# Other.net
KiCad netlist of a schematic drawn in Altium Designer
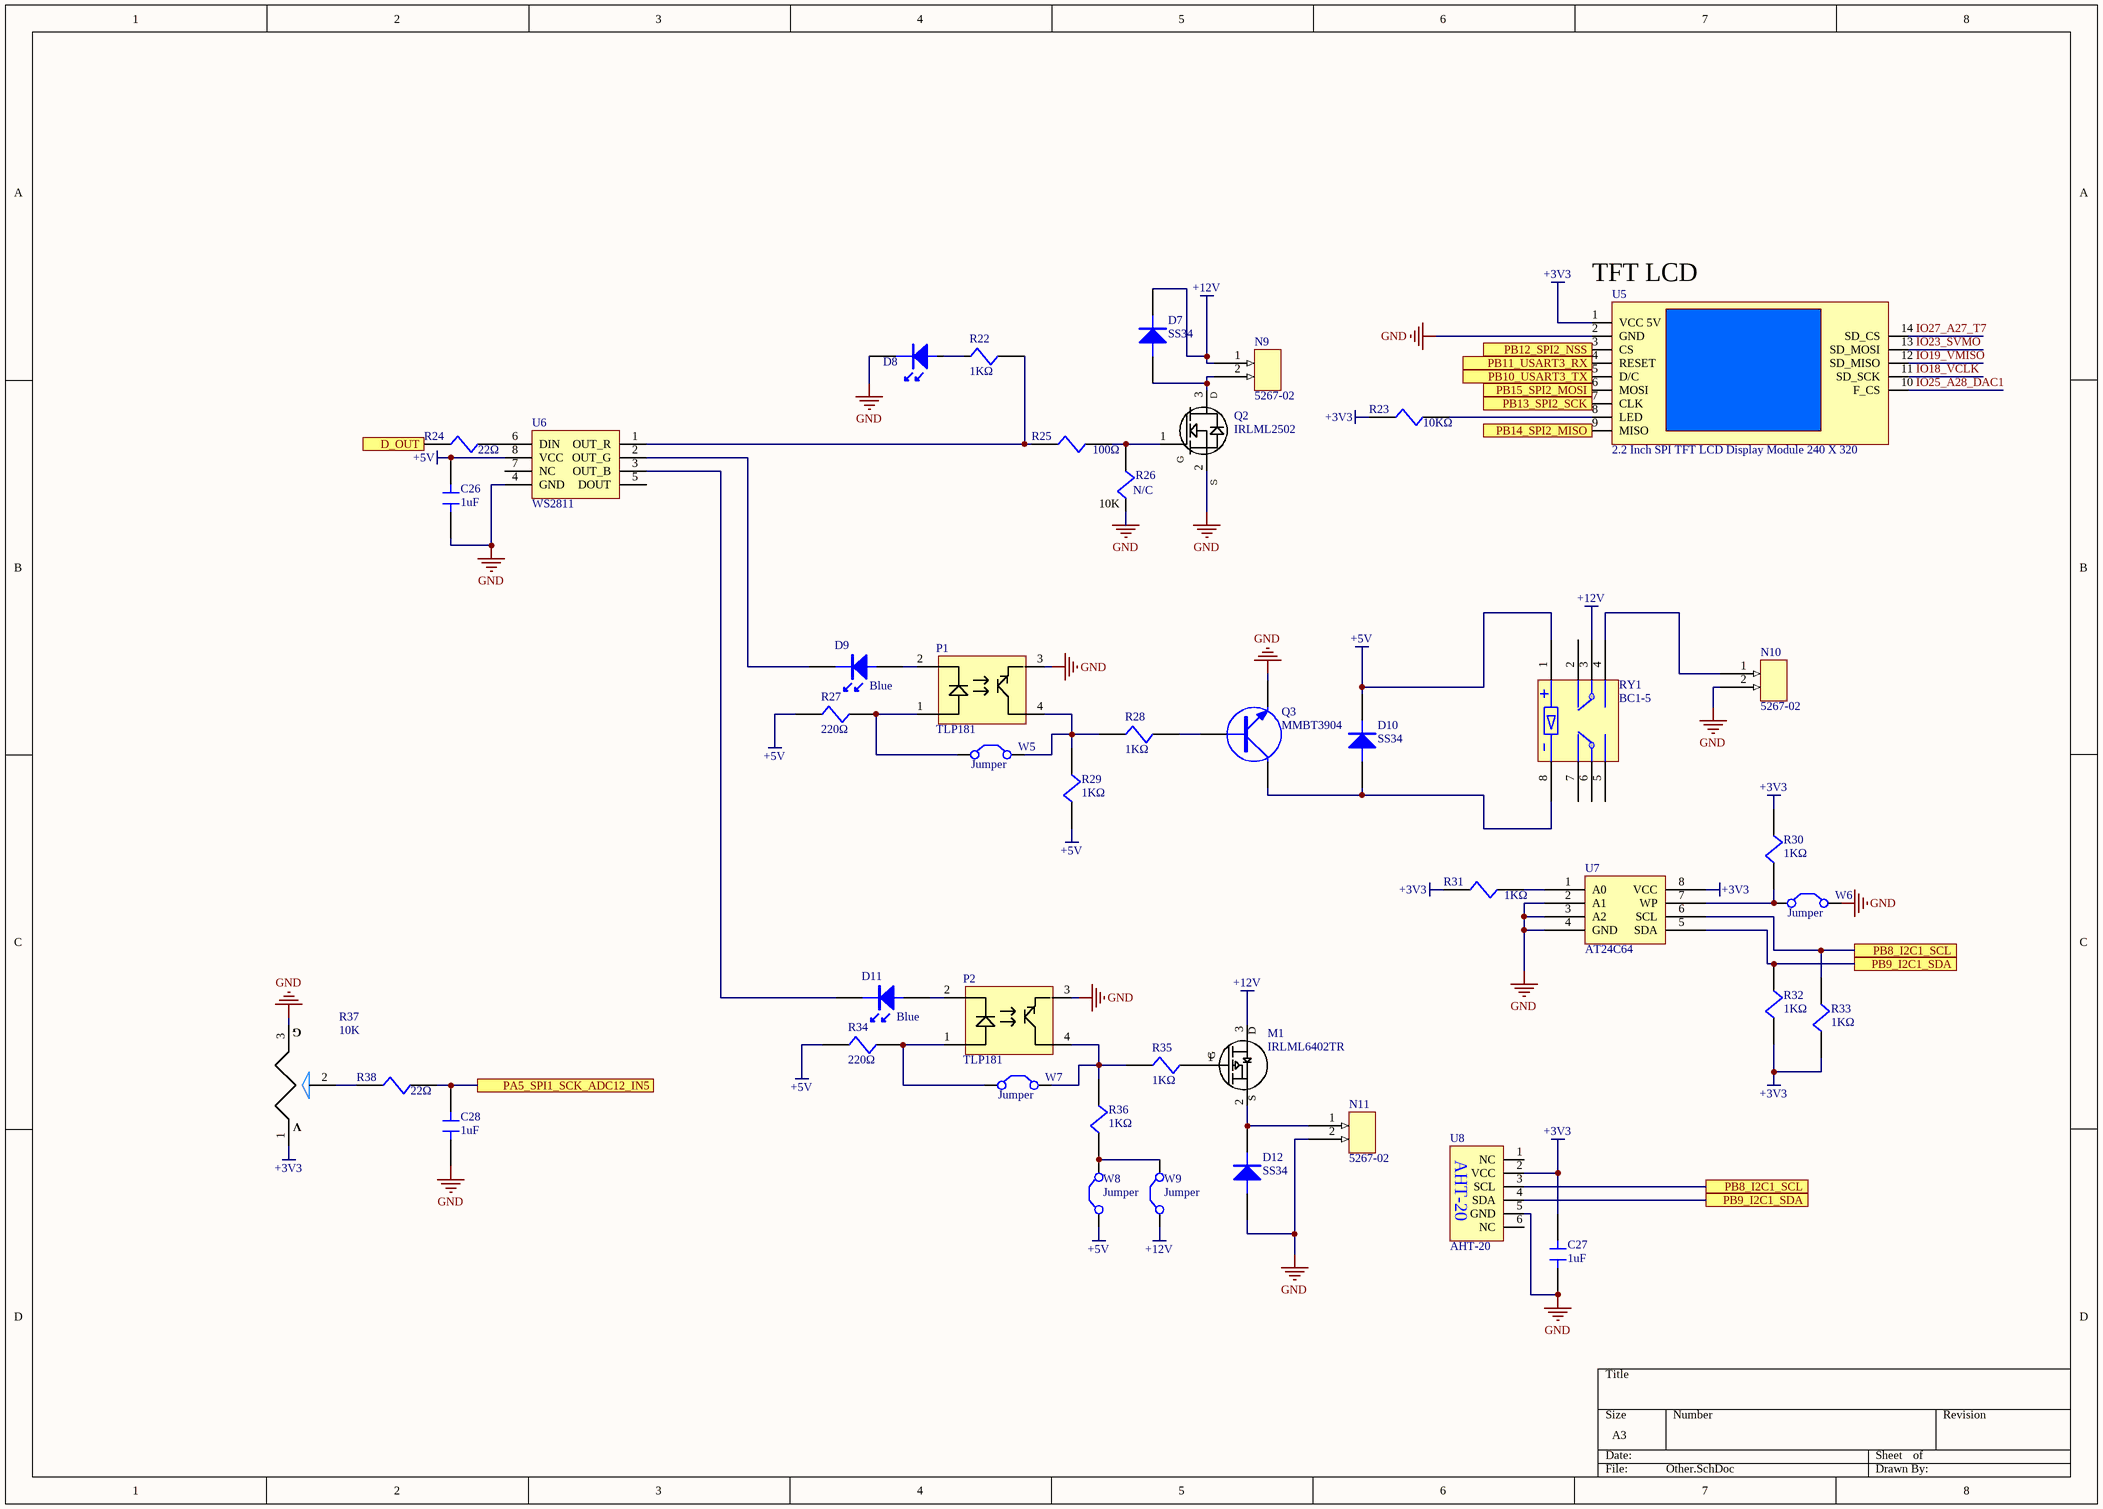
[diagram p0: Other.SchDoc]

(export (version "E")
  (design (tool "Eeschema 10.0.6"))
  (components
    (comp (ref "C26")
      (value "Chip Capacitor")
      (footprint "1608-C")
      (description "Capacitor, 1608 type")
      (fields (field (name "PART NUMBER") "1uF"))
      (libsource (lib "*") (part "CAP"))
    )
    (comp (ref "C27")
      (value "Chip Capacitor")
      (footprint "1608-C")
      (description "Capacitor, 1608 type")
      (fields (field (name "PART NUMBER") "1uF"))
      (libsource (lib "*") (part "CAP"))
    )
    (comp (ref "C28")
      (value "Chip Capacitor")
      (footprint "1608-C")
      (description "Capacitor, 1608 type")
      (fields (field (name "PART NUMBER") "1uF"))
      (libsource (lib "*") (part "CAP"))
    )
    (comp (ref "D7")
      (value "DIODE")
      (footprint "SS34")
      (fields (field (name "PART NUMBER") "SS34"))
      (libsource (lib "SCH_LIB") (part "DIODE"))
    )
    (comp (ref "D8")
      (value "LED")
      (footprint "1608-LED")
      (description "Green, 1608. SMD")
      (libsource (lib "SCH_LIB") (part "LED"))
    )
    (comp (ref "D9")
      (value "Chip LED")
      (footprint "1608-LED")
      (description "1608 Chip LED")
      (fields (field (name "PART NUMBER") "Blue"))
      (libsource (lib "SCH_LIB") (part "LED"))
    )
    (comp (ref "D10")
      (value "DIODE")
      (footprint "SS34")
      (fields (field (name "PART NUMBER") "SS34"))
      (libsource (lib "SCH_LIB") (part "DIODE"))
    )
    (comp (ref "D11")
      (value "Chip LED")
      (footprint "1608-LED")
      (description "1608 Chip LED")
      (fields (field (name "PART NUMBER") "Blue"))
      (libsource (lib "SCH_LIB") (part "LED"))
    )
    (comp (ref "D12")
      (value "DIODE")
      (footprint "SS34")
      (fields (field (name "PART NUMBER") "SS34"))
      (libsource (lib "SCH_LIB") (part "DIODE"))
    )
    (comp (ref "M1")
      (value "MOSPET-P")
      (footprint "Micro3")
      (description "P-Channel MOSFET")
      (fields (field (name "PART NUMBER") "IRLML6402TR"))
      (libsource (lib "SEMIN_LIB_SCH") (part "MOSPET-P"))
    )
    (comp (ref "N9")
      (value "CONNECTOR")
      (footprint "5267-02")
      (description "Molex")
      (fields (field (name "PART NUMBER") "5267-02"))
      (libsource (lib "SCH_LIB") (part "CON2"))
    )
    (comp (ref "N10")
      (value "CONNECTOR")
      (footprint "5267-02")
      (description "Molex")
      (fields (field (name "PART NUMBER") "5267-02"))
      (libsource (lib "SCH_LIB") (part "CON2"))
    )
    (comp (ref "N11")
      (value "CONNECTOR")
      (footprint "5267-02")
      (description "Molex")
      (fields (field (name "PART NUMBER") "5267-02"))
      (libsource (lib "SCH_LIB") (part "CON2"))
    )
    (comp (ref "P1")
      (value "Photo_Coupler")
      (footprint "TLP181")
      (description "1CH_small coupler")
      (fields (field (name "PART NUMBER") "TLP181"))
      (libsource (lib "SEMIN_LIB_SCH") (part "Photo_Coupler"))
    )
    (comp (ref "P2")
      (value "Photo_Coupler")
      (footprint "TLP181")
      (description "1CH_small coupler")
      (fields (field (name "PART NUMBER") "TLP181"))
      (libsource (lib "SEMIN_LIB_SCH") (part "Photo_Coupler"))
    )
    (comp (ref "Q2")
      (value "N_FET")
      (footprint "SOT_23_BIG")
      (description "N Chnel FET")
      (fields (field (name "PART NUMBER") "IRLML2502"))
      (libsource (lib "SEMIN_LIB_SCH") (part "IRLML2502"))
    )
    (comp (ref "Q3")
      (value "NPN TR")
      (footprint "SOT-23TR")
      (description "Transistor")
      (fields (field (name "PART NUMBER") "MMBT3904"))
      (libsource (lib "SCH_LIB") (part "TR(NPN)"))
    )
    (comp (ref "R22")
      (value "Chip Resistor")
      (footprint "1608-R")
      (description "Resistor, 1608 type")
      (fields (field (name "PART NUMBER") "1KΩ"))
      (libsource (lib "*") (part "RES1"))
    )
    (comp (ref "R23")
      (value "Chip Resistor")
      (footprint "1608-R")
      (description "Resistor, 1608 type")
      (fields (field (name "PART NUMBER") "10KΩ"))
      (libsource (lib "*") (part "RES1"))
    )
    (comp (ref "R24")
      (value "Chip Resistor")
      (footprint "1608-R")
      (description "Resistor, 1608 type")
      (fields (field (name "PART NUMBER") "22Ω"))
      (libsource (lib "*") (part "RES1"))
    )
    (comp (ref "R25")
      (value "Chip Resistor")
      (footprint "1608-R")
      (description "Resistor, 1608 type")
      (fields (field (name "PART NUMBER") "100Ω"))
      (libsource (lib "*") (part "RES1"))
    )
    (comp (ref "R26")
      (value "Chip Resistor")
      (footprint "1608-R")
      (description "Resistor, 1608 type")
      (fields (field (name "PART NUMBER") "N/C"))
      (libsource (lib "*") (part "RES1"))
    )
    (comp (ref "R27")
      (value "Chip Resistor")
      (footprint "1608-R")
      (description "Resistor, 1608 type")
      (fields (field (name "PART NUMBER") "220Ω"))
      (libsource (lib "*") (part "RES1"))
    )
    (comp (ref "R28")
      (value "Chip Resistor")
      (footprint "1608-R")
      (description "Resistor, 1608 type")
      (fields (field (name "PART NUMBER") "1KΩ"))
      (libsource (lib "*") (part "RES1"))
    )
    (comp (ref "R29")
      (value "Chip Resistor")
      (footprint "1608-R")
      (description "Resistor, 1608 type")
      (fields (field (name "PART NUMBER") "1KΩ"))
      (libsource (lib "*") (part "RES1"))
    )
    (comp (ref "R30")
      (value "Chip Resistor")
      (footprint "1608-R")
      (description "Resistor, 1608 type")
      (fields (field (name "PART NUMBER") "1KΩ"))
      (libsource (lib "*") (part "RES1"))
    )
    (comp (ref "R31")
      (value "Chip Resistor")
      (footprint "1608-R")
      (description "Resistor, 1608 type")
      (fields (field (name "PART NUMBER") "1KΩ"))
      (libsource (lib "*") (part "RES1"))
    )
    (comp (ref "R32")
      (value "Chip Resistor")
      (footprint "1608-R")
      (description "Resistor, 1608 type")
      (fields (field (name "PART NUMBER") "1KΩ"))
      (libsource (lib "*") (part "RES1"))
    )
    (comp (ref "R33")
      (value "Chip Resistor")
      (footprint "1608-R")
      (description "Resistor, 1608 type")
      (fields (field (name "PART NUMBER") "1KΩ"))
      (libsource (lib "*") (part "RES1"))
    )
    (comp (ref "R34")
      (value "Chip Resistor")
      (footprint "1608-R")
      (description "Resistor, 1608 type")
      (fields (field (name "PART NUMBER") "220Ω"))
      (libsource (lib "*") (part "RES1"))
    )
    (comp (ref "R35")
      (value "Chip Resistor")
      (footprint "1608-R")
      (description "Resistor, 1608 type")
      (fields (field (name "PART NUMBER") "1KΩ"))
      (libsource (lib "*") (part "RES1"))
    )
    (comp (ref "R36")
      (value "Chip Resistor")
      (footprint "1608-R")
      (description "Resistor, 1608 type")
      (fields (field (name "PART NUMBER") "1KΩ"))
      (libsource (lib "*") (part "RES1"))
    )
    (comp (ref "R37")
      (value "10K")
      (footprint "RES_POT_RV12V-15RS")
      (description "RV09H-20SQ 10KΩ")
      (libsource (lib "SEMIN_LIB_SCH") (part "RES-POT"))
    )
    (comp (ref "R38")
      (value "Chip Resistor")
      (footprint "1608-R")
      (description "Resistor, 1608 type")
      (fields (field (name "PART NUMBER") "22Ω"))
      (libsource (lib "*") (part "RES1"))
    )
    (comp (ref "RY1")
      (value "Relay")
      (footprint "RELAY_BC1")
      (description "5V, dual, DIP")
      (fields (field (name "PART NUMBER") "BC1-5"))
      (libsource (lib "SCH_LIB") (part "RELAY"))
    )
    (comp (ref "U5")
      (value "TFT LCD")
      (footprint "LCD_TFT_2.2")
      (description "TFT 2.2 LCD 320 X 240")
      (fields (field (name "PART NUMBER") "2.2 Inch SPI TFT LCD Display Module 240 X 320"))
      (libsource (lib "SEMIN_LIB_SCH") (part "LCD_TFT_2.2"))
    )
    (comp (ref "U6")
      (value "Driver")
      (footprint "SOP-08_mini")
      (description "PWM Driver")
      (fields (field (name "PART NUMBER") "WS2811"))
      (libsource (lib "SEMIN_LIB_SCH") (part "WS2811"))
    )
    (comp (ref "U7") (value "AT24C64") (footprint "SOIC-8") (libsource (lib "SCH_LIB") (part "AT24C64")))
    (comp (ref "U8")
      (value "Sensor")
      (footprint "AHT-20")
      (description "Temperature and Humidity sensor")
      (fields (field (name "PART NUMBER") "AHT-20"))
      (libsource (lib "SEMIN_LIB_SCH") (part "AHT-20"))
    )
    (comp (ref "W5")
      (value "Jumper")
      (footprint "jp")
      (description "Jumper Wire")
      (fields (field (name "PART NUMBER") "NC") (field (name "PUBLISHER") "Altium Limited"))
      (libsource (lib "Miscellaneous Devices") (part "Jumper"))
    )
    (comp (ref "W6")
      (value "Jumper")
      (footprint "jp")
      (description "Jumper Wire")
      (fields (field (name "PART NUMBER") "NC") (field (name "PUBLISHER") "Altium Limited"))
      (libsource (lib "Miscellaneous Devices") (part "Jumper"))
    )
    (comp (ref "W7")
      (value "Jumper")
      (footprint "jp")
      (description "Jumper Wire")
      (fields (field (name "PART NUMBER") "NC") (field (name "PUBLISHER") "Altium Limited"))
      (libsource (lib "Miscellaneous Devices") (part "Jumper"))
    )
    (comp (ref "W8")
      (value "Jumper")
      (footprint "jp")
      (description "Jumper Wire")
      (fields (field (name "PART NUMBER") "NC") (field (name "PUBLISHER") "Altium Limited"))
      (libsource (lib "Miscellaneous Devices") (part "Jumper"))
    )
    (comp (ref "W9")
      (value "Jumper")
      (footprint "jp")
      (description "Jumper Wire")
      (fields (field (name "PART NUMBER") "NC") (field (name "PUBLISHER") "Altium Limited"))
      (libsource (lib "Miscellaneous Devices") (part "Jumper"))
    )
  )
  (nets
    (net (code "1") (name "+3V3") (class "Default")
      (node (ref "C27") (pin "2") (pinfunction "2_2") (pintype "passive"))
      (node (ref "R23") (pin "1") (pinfunction "1_1") (pintype "passive"))
      (node (ref "R30") (pin "2") (pinfunction "2_2") (pintype "passive"))
      (node (ref "R31") (pin "1") (pinfunction "1_1") (pintype "passive"))
      (node (ref "R32") (pin "1") (pinfunction "1_1") (pintype "passive"))
      (node (ref "R33") (pin "1") (pinfunction "1_1") (pintype "passive"))
      (node (ref "R37") (pin "1") (pinfunction "1_1") (pintype "passive"))
      (node (ref "U5") (pin "1") (pinfunction "VCC_5V_1") (pintype "passive"))
      (node (ref "U7") (pin "8") (pinfunction "VCC_8") (pintype "passive"))
      (node (ref "U8") (pin "2") (pinfunction "VCC_2") (pintype "passive"))
    )
    (net (code "2") (name "+5V") (class "Default")
      (node (ref "C26") (pin "1") (pinfunction "1_1") (pintype "passive"))
      (node (ref "D10") (pin "2") (pinfunction "K_2") (pintype "passive"))
      (node (ref "R27") (pin "2") (pinfunction "2_2") (pintype "passive"))
      (node (ref "R29") (pin "2") (pinfunction "2_2") (pintype "passive"))
      (node (ref "R34") (pin "2") (pinfunction "2_2") (pintype "passive"))
      (node (ref "RY1") (pin "1") (pintype "passive"))
      (node (ref "U6") (pin "8") (pinfunction "VCC_8") (pintype "passive"))
      (node (ref "W8") (pin "1") (pinfunction "C1_1") (pintype "passive"))
    )
    (net (code "3") (name "+12V") (class "Default")
      (node (ref "D7") (pin "2") (pinfunction "K_2") (pintype "passive"))
      (node (ref "M1") (pin "3") (pinfunction "D_3") (pintype "passive"))
      (node (ref "N9") (pin "1") (pintype "input"))
      (node (ref "RY1") (pin "3") (pintype "passive"))
      (node (ref "W9") (pin "1") (pinfunction "C1_1") (pintype "passive"))
    )
    (net (code "4") (name "/D_OUT") (class "Default")
      (node (ref "R24") (pin "2") (pinfunction "2_2") (pintype "passive"))
    )
    (net (code "5") (name "/IO18_VCLK") (class "Default")
      (node (ref "U5") (pin "11") (pinfunction "SD_SCK_11") (pintype "passive"))
    )
    (net (code "6") (name "/IO19_VMISO") (class "Default")
      (node (ref "U5") (pin "12") (pinfunction "SD_MISO_12") (pintype "passive"))
    )
    (net (code "7") (name "/IO23_SVMO") (class "Default")
      (node (ref "U5") (pin "13") (pinfunction "SD_MOSI_13") (pintype "passive"))
    )
    (net (code "8") (name "/IO25_A28_DAC1") (class "Default")
      (node (ref "U5") (pin "10") (pinfunction "F_CS_10") (pintype "passive"))
    )
    (net (code "9") (name "/IO27_A27_T7") (class "Default")
      (node (ref "U5") (pin "14") (pinfunction "SD_CS_14") (pintype "passive"))
    )
    (net (code "10") (name "/PA5_SPI1_SCK_ADC12_IN5") (class "Default")
      (node (ref "C28") (pin "1") (pinfunction "1_1") (pintype "passive"))
      (node (ref "R38") (pin "1") (pinfunction "1_1") (pintype "passive"))
    )
    (net (code "11") (name "/PB8_I2C1_SCL") (class "Default")
      (node (ref "R33") (pin "2") (pinfunction "2_2") (pintype "passive"))
      (node (ref "U7") (pin "6") (pinfunction "SCL_6") (pintype "passive"))
      (node (ref "U8") (pin "3") (pinfunction "SCL_3") (pintype "passive"))
    )
    (net (code "12") (name "/PB9_I2C1_SDA") (class "Default")
      (node (ref "R32") (pin "2") (pinfunction "2_2") (pintype "passive"))
      (node (ref "U7") (pin "5") (pinfunction "SDA_5") (pintype "passive"))
      (node (ref "U8") (pin "4") (pinfunction "SDA_4") (pintype "passive"))
    )
    (net (code "13") (name "/PB10_USART3_TX") (class "Default")
      (node (ref "U5") (pin "5") (pinfunction "D/C_5") (pintype "passive"))
    )
    (net (code "14") (name "/PB11_USART3_RX") (class "Default")
      (node (ref "U5") (pin "4") (pinfunction "RESET_4") (pintype "passive"))
    )
    (net (code "15") (name "/PB12_SPI2_NSS") (class "Default")
      (node (ref "U5") (pin "3") (pinfunction "CS_3") (pintype "passive"))
    )
    (net (code "16") (name "/PB13_SPI2_SCK") (class "Default")
      (node (ref "U5") (pin "7") (pinfunction "CLK_7") (pintype "passive"))
    )
    (net (code "17") (name "/PB14_SPI2_MISO") (class "Default")
      (node (ref "U5") (pin "9") (pinfunction "MISO_9") (pintype "passive"))
    )
    (net (code "18") (name "/PB15_SPI2_MOSI") (class "Default")
      (node (ref "U5") (pin "6") (pinfunction "MOSI_6") (pintype "passive"))
    )
    (net (code "19") (name "GND") (class "Default")
      (node (ref "C26") (pin "2") (pinfunction "2_2") (pintype "passive"))
      (node (ref "C27") (pin "1") (pinfunction "1_1") (pintype "passive"))
      (node (ref "C28") (pin "2") (pinfunction "2_2") (pintype "passive"))
      (node (ref "D12") (pin "1") (pinfunction "A_1") (pintype "passive"))
      (node (ref "D8") (pin "2") (pinfunction "2_2") (pintype "passive"))
      (node (ref "N10") (pin "2") (pintype "input"))
      (node (ref "N11") (pin "2") (pintype "input"))
      (node (ref "P1") (pin "3") (pinfunction "3_3") (pintype "passive"))
      (node (ref "P2") (pin "3") (pinfunction "3_3") (pintype "passive"))
      (node (ref "Q2") (pin "2") (pinfunction "2_2") (pintype "passive"))
      (node (ref "Q3") (pin "3") (pinfunction "E_3") (pintype "passive"))
      (node (ref "R26") (pin "1") (pinfunction "1_1") (pintype "passive"))
      (node (ref "R37") (pin "3") (pinfunction "3_3") (pintype "passive"))
      (node (ref "U5") (pin "2") (pinfunction "GND_2") (pintype "passive"))
      (node (ref "U6") (pin "4") (pinfunction "GND_4") (pintype "passive"))
      (node (ref "U7") (pin "2") (pinfunction "A1_2") (pintype "passive"))
      (node (ref "U7") (pin "3") (pinfunction "A2_3") (pintype "passive"))
      (node (ref "U7") (pin "4") (pinfunction "GND_4") (pintype "passive"))
      (node (ref "U8") (pin "5") (pinfunction "GND_5") (pintype "passive"))
      (node (ref "W6") (pin "2") (pinfunction "C2_2") (pintype "passive"))
    )
    (net (code "20") (name "Net-(D7-A)") (class "Default")
      (node (ref "D7") (pin "1") (pinfunction "A_1") (pintype "passive"))
      (node (ref "N9") (pin "2") (pintype "input"))
      (node (ref "Q2") (pin "3") (pinfunction "3_3") (pintype "passive"))
    )
    (net (code "21") (name "Net-(D8-Pad1)") (class "Default")
      (node (ref "D8") (pin "1") (pinfunction "1_1") (pintype "passive"))
      (node (ref "R22") (pin "2") (pinfunction "2_2") (pintype "passive"))
    )
    (net (code "22") (name "Net-(D9-Pad1)") (class "Default")
      (node (ref "D9") (pin "1") (pinfunction "1_1") (pintype "passive"))
      (node (ref "P1") (pin "2") (pinfunction "2_2") (pintype "passive"))
    )
    (net (code "23") (name "Net-(D10-A)") (class "Default")
      (node (ref "D10") (pin "1") (pinfunction "A_1") (pintype "passive"))
      (node (ref "Q3") (pin "2") (pinfunction "C_2") (pintype "passive"))
      (node (ref "RY1") (pin "8") (pintype "passive"))
    )
    (net (code "24") (name "Net-(D11-Pad1)") (class "Default")
      (node (ref "D11") (pin "1") (pinfunction "1_1") (pintype "passive"))
      (node (ref "P2") (pin "2") (pinfunction "2_2") (pintype "passive"))
    )
    (net (code "25") (name "Net-(D12-K)") (class "Default")
      (node (ref "D12") (pin "2") (pinfunction "K_2") (pintype "passive"))
      (node (ref "M1") (pin "2") (pinfunction "S_2") (pintype "passive"))
      (node (ref "N11") (pin "1") (pintype "input"))
    )
    (net (code "26") (name "Net-(M1-G)") (class "Default")
      (node (ref "M1") (pin "1") (pinfunction "G_1") (pintype "passive"))
      (node (ref "R35") (pin "2") (pinfunction "2_2") (pintype "passive"))
    )
    (net (code "27") (name "Net-(N10-Pad1)") (class "Default")
      (node (ref "N10") (pin "1") (pintype "input"))
      (node (ref "RY1") (pin "4") (pintype "passive"))
    )
    (net (code "28") (name "Net-(Q2-4)") (class "Default")
      (node (ref "Q2") (pin "1") (pinfunction "4_1") (pintype "passive"))
      (node (ref "R25") (pin "2") (pinfunction "2_2") (pintype "passive"))
      (node (ref "R26") (pin "2") (pinfunction "2_2") (pintype "passive"))
    )
    (net (code "29") (name "Net-(Q3-B)") (class "Default")
      (node (ref "Q3") (pin "1") (pinfunction "B_1") (pintype "passive"))
      (node (ref "R28") (pin "2") (pinfunction "2_2") (pintype "passive"))
    )
    (net (code "30") (name "Net-(R37-Pad2)") (class "Default")
      (node (ref "R37") (pin "2") (pinfunction "2_2") (pintype "passive"))
      (node (ref "R38") (pin "2") (pinfunction "2_2") (pintype "passive"))
    )
    (net (code "31") (name "Net-(U5-LED)") (class "Default")
      (node (ref "R23") (pin "2") (pinfunction "2_2") (pintype "passive"))
      (node (ref "U5") (pin "8") (pinfunction "LED_8") (pintype "passive"))
    )
    (net (code "32") (name "Net-(U6-DIN)") (class "Default")
      (node (ref "R24") (pin "1") (pinfunction "1_1") (pintype "passive"))
      (node (ref "U6") (pin "6") (pinfunction "DIN_6") (pintype "passive"))
    )
    (net (code "33") (name "Net-(U6-OUT_B)") (class "Default")
      (node (ref "D11") (pin "2") (pinfunction "2_2") (pintype "passive"))
      (node (ref "U6") (pin "3") (pinfunction "OUT_B_3") (pintype "passive"))
    )
    (net (code "34") (name "Net-(U6-OUT_G)") (class "Default")
      (node (ref "D9") (pin "2") (pinfunction "2_2") (pintype "passive"))
      (node (ref "U6") (pin "2") (pinfunction "OUT_G_2") (pintype "passive"))
    )
    (net (code "35") (name "Net-(U6-OUT_R)") (class "Default")
      (node (ref "R22") (pin "1") (pinfunction "1_1") (pintype "passive"))
      (node (ref "R25") (pin "1") (pinfunction "1_1") (pintype "passive"))
      (node (ref "U6") (pin "1") (pinfunction "OUT_R_1") (pintype "passive"))
    )
    (net (code "36") (name "Net-(U7-A0)") (class "Default")
      (node (ref "R31") (pin "2") (pinfunction "2_2") (pintype "passive"))
      (node (ref "U7") (pin "1") (pinfunction "A0_1") (pintype "passive"))
    )
    (net (code "37") (name "Net-(U7-WP)") (class "Default")
      (node (ref "R30") (pin "1") (pinfunction "1_1") (pintype "passive"))
      (node (ref "U7") (pin "7") (pinfunction "WP_7") (pintype "passive"))
      (node (ref "W6") (pin "1") (pinfunction "C1_1") (pintype "passive"))
    )
    (net (code "38") (name "Net-(W5-C1)") (class "Default")
      (node (ref "P1") (pin "1") (pintype "passive"))
      (node (ref "R27") (pin "1") (pinfunction "1_1") (pintype "passive"))
      (node (ref "W5") (pin "1") (pinfunction "C1_1") (pintype "passive"))
    )
    (net (code "39") (name "Net-(W5-C2)") (class "Default")
      (node (ref "P1") (pin "4") (pinfunction "4_4") (pintype "passive"))
      (node (ref "R28") (pin "1") (pinfunction "1_1") (pintype "passive"))
      (node (ref "R29") (pin "1") (pinfunction "1_1") (pintype "passive"))
      (node (ref "W5") (pin "2") (pinfunction "C2_2") (pintype "passive"))
    )
    (net (code "40") (name "Net-(W7-C1)") (class "Default")
      (node (ref "P2") (pin "1") (pintype "passive"))
      (node (ref "R34") (pin "1") (pinfunction "1_1") (pintype "passive"))
      (node (ref "W7") (pin "1") (pinfunction "C1_1") (pintype "passive"))
    )
    (net (code "41") (name "Net-(W7-C2)") (class "Default")
      (node (ref "P2") (pin "4") (pinfunction "4_4") (pintype "passive"))
      (node (ref "R35") (pin "1") (pinfunction "1_1") (pintype "passive"))
      (node (ref "R36") (pin "1") (pinfunction "1_1") (pintype "passive"))
      (node (ref "W7") (pin "2") (pinfunction "C2_2") (pintype "passive"))
    )
    (net (code "42") (name "Net-(W8-C2)") (class "Default")
      (node (ref "R36") (pin "2") (pinfunction "2_2") (pintype "passive"))
      (node (ref "W8") (pin "2") (pinfunction "C2_2") (pintype "passive"))
      (node (ref "W9") (pin "2") (pinfunction "C2_2") (pintype "passive"))
    )
    (net (code "43") (name "unconnected-(RY1-Pad2)") (class "Default")
      (node (ref "RY1") (pin "2") (pintype "passive"))
    )
    (net (code "44") (name "unconnected-(RY1-Pad5)") (class "Default")
      (node (ref "RY1") (pin "5") (pintype "passive"))
    )
    (net (code "45") (name "unconnected-(RY1-Pad6)") (class "Default")
      (node (ref "RY1") (pin "6") (pintype "passive"))
    )
    (net (code "46") (name "unconnected-(RY1-Pad7)") (class "Default")
      (node (ref "RY1") (pin "7") (pintype "passive"))
    )
    (net (code "47") (name "unconnected-(U6-DOUT-Pad5)") (class "Default")
      (node (ref "U6") (pin "5") (pinfunction "DOUT_5") (pintype "passive"))
    )
    (net (code "48") (name "unconnected-(U6-NC-Pad7)") (class "Default")
      (node (ref "U6") (pin "7") (pinfunction "NC_7") (pintype "passive"))
    )
    (net (code "49") (name "unconnected-(U8-NC-Pad1)") (class "Default")
      (node (ref "U8") (pin "1") (pinfunction "NC_1") (pintype "passive"))
    )
    (net (code "50") (name "unconnected-(U8-NC-Pad6)") (class "Default")
      (node (ref "U8") (pin "6") (pinfunction "NC_6") (pintype "passive"))
    )
  )
)
